# shifter.net
KiCad netlist of a schematic drawn in EAGLE
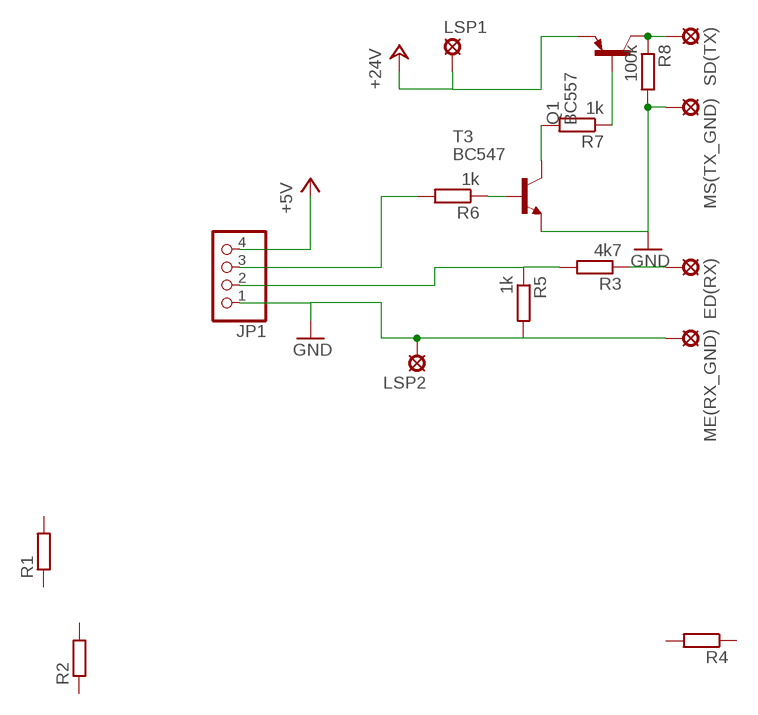
[diagram p0: schematic, sheet 1]

(export (version "E")
  (design (tool "Eeschema 10.0.6"))
  (components
    (comp (ref "ED(RX)")
      (value "LSP10")
      (footprint "eagle-import:LSP10")
      (libsource (lib "eagle-import") (part "LSP10"))
    )
    (comp (ref "JP1")
      (value "PINHD-1X4")
      (footprint "eagle-import:1X04")
      (libsource (lib "eagle-import") (part "PINHD-1X4"))
    )
    (comp (ref "LSP1")
      (value "LSP10")
      (footprint "eagle-import:LSP10")
      (libsource (lib "eagle-import") (part "LSP10"))
    )
    (comp (ref "LSP2")
      (value "LSP10")
      (footprint "eagle-import:LSP10")
      (libsource (lib "eagle-import") (part "LSP10"))
    )
    (comp (ref "ME(RX_GND)")
      (value "LSP10")
      (footprint "eagle-import:LSP10")
      (libsource (lib "eagle-import") (part "LSP10"))
    )
    (comp (ref "MS(TX_GND)")
      (value "LSP10")
      (footprint "eagle-import:LSP10")
      (libsource (lib "eagle-import") (part "LSP10"))
    )
    (comp (ref "Q1")
      (value "BC557")
      (footprint "eagle-import:TO92")
      (libsource (lib "eagle-import") (part "BC557"))
    )
    (comp (ref "R1")
      (value "R-EU_M0805")
      (footprint "eagle-import:M0805")
      (libsource (lib "eagle-import") (part "R-EU_M0805"))
    )
    (comp (ref "R2")
      (value "R-EU_M0805")
      (footprint "eagle-import:M0805")
      (libsource (lib "eagle-import") (part "R-EU_M0805"))
    )
    (comp (ref "R3")
      (value "4k7")
      (footprint "eagle-import:M0805")
      (libsource (lib "eagle-import") (part "R-EU_M0805"))
    )
    (comp (ref "R4")
      (value "R-EU_M0805")
      (footprint "eagle-import:M0805")
      (libsource (lib "eagle-import") (part "R-EU_M0805"))
    )
    (comp (ref "R5")
      (value "1k")
      (footprint "eagle-import:M0805")
      (libsource (lib "eagle-import") (part "R-EU_M0805"))
    )
    (comp (ref "R6")
      (value "1k")
      (footprint "eagle-import:M0805")
      (libsource (lib "eagle-import") (part "R-EU_M0805"))
    )
    (comp (ref "R7")
      (value "1k")
      (footprint "eagle-import:M0805")
      (libsource (lib "eagle-import") (part "R-EU_M0805"))
    )
    (comp (ref "R8")
      (value "100k")
      (footprint "eagle-import:M0805")
      (libsource (lib "eagle-import") (part "R-EU_M0805"))
    )
    (comp (ref "SD(TX)")
      (value "LSP10")
      (footprint "eagle-import:LSP10")
      (libsource (lib "eagle-import") (part "LSP10"))
    )
    (comp (ref "T3")
      (value "BC547")
      (footprint "eagle-import:TO92")
      (libsource (lib "eagle-import") (part "BC547"))
    )
  )
  (nets
    (net (code "1") (name "+5V") (class "Default")
      (node (ref "JP1") (pin "4") (pinfunction "4_4") (pintype "passive"))
    )
    (net (code "2") (name "+24V") (class "Default")
      (node (ref "LSP1") (pin "MP") (pinfunction "MP_MP") (pintype "passive"))
      (node (ref "Q1") (pin "1") (pinfunction "E_1") (pintype "passive"))
    )
    (net (code "3") (name "GND") (class "Default")
      (node (ref "JP1") (pin "1") (pinfunction "1_1") (pintype "passive"))
      (node (ref "LSP2") (pin "MP") (pinfunction "MP_MP") (pintype "passive"))
      (node (ref "ME(RX_GND)") (pin "MP") (pinfunction "MP_MP") (pintype "passive"))
      (node (ref "MS(TX_GND)") (pin "MP") (pinfunction "MP_MP") (pintype "passive"))
      (node (ref "R5") (pin "2") (pinfunction "2_2") (pintype "passive"))
      (node (ref "R8") (pin "2") (pinfunction "2_2") (pintype "passive"))
      (node (ref "T3") (pin "1") (pinfunction "E_1") (pintype "passive"))
    )
    (net (code "4") (name "Net-(ED(RX)-PadMP)") (class "Default")
      (node (ref "ED(RX)") (pin "MP") (pinfunction "MP_MP") (pintype "passive"))
      (node (ref "R3") (pin "1") (pinfunction "1_1") (pintype "passive"))
    )
    (net (code "5") (name "Net-(JP1-Pad2)") (class "Default")
      (node (ref "JP1") (pin "2") (pinfunction "2_2") (pintype "passive"))
      (node (ref "R3") (pin "2") (pinfunction "2_2") (pintype "passive"))
      (node (ref "R5") (pin "1") (pinfunction "1_1") (pintype "passive"))
    )
    (net (code "6") (name "Net-(JP1-Pad3)") (class "Default")
      (node (ref "JP1") (pin "3") (pinfunction "3_3") (pintype "passive"))
      (node (ref "R6") (pin "2") (pinfunction "2_2") (pintype "passive"))
    )
    (net (code "7") (name "Net-(Q1-B)") (class "Default")
      (node (ref "Q1") (pin "2") (pinfunction "B_2") (pintype "passive"))
      (node (ref "R7") (pin "1") (pinfunction "1_1") (pintype "passive"))
    )
    (net (code "8") (name "Net-(Q1-C)") (class "Default")
      (node (ref "Q1") (pin "3") (pinfunction "C_3") (pintype "passive"))
      (node (ref "R8") (pin "1") (pinfunction "1_1") (pintype "passive"))
      (node (ref "SD(TX)") (pin "MP") (pinfunction "MP_MP") (pintype "passive"))
    )
    (net (code "9") (name "Net-(T3-B)") (class "Default")
      (node (ref "R6") (pin "1") (pinfunction "1_1") (pintype "passive"))
      (node (ref "T3") (pin "2") (pinfunction "B_2") (pintype "passive"))
    )
    (net (code "10") (name "Net-(T3-C)") (class "Default")
      (node (ref "R7") (pin "2") (pinfunction "2_2") (pintype "passive"))
      (node (ref "T3") (pin "3") (pinfunction "C_3") (pintype "passive"))
    )
    (net (code "11") (name "unconnected-(R1-Pad1)") (class "Default")
      (node (ref "R1") (pin "1") (pinfunction "1_1") (pintype "passive"))
    )
    (net (code "12") (name "unconnected-(R1-Pad2)") (class "Default")
      (node (ref "R1") (pin "2") (pinfunction "2_2") (pintype "passive"))
    )
    (net (code "13") (name "unconnected-(R2-Pad1)") (class "Default")
      (node (ref "R2") (pin "1") (pinfunction "1_1") (pintype "passive"))
    )
    (net (code "14") (name "unconnected-(R2-Pad2)") (class "Default")
      (node (ref "R2") (pin "2") (pinfunction "2_2") (pintype "passive"))
    )
    (net (code "15") (name "unconnected-(R4-Pad1)") (class "Default")
      (node (ref "R4") (pin "1") (pinfunction "1_1") (pintype "passive"))
    )
    (net (code "16") (name "unconnected-(R4-Pad2)") (class "Default")
      (node (ref "R4") (pin "2") (pinfunction "2_2") (pintype "passive"))
    )
  )
)
